# OV5640_Module_Connect.net
KiCad netlist of a schematic drawn in Altium Designer
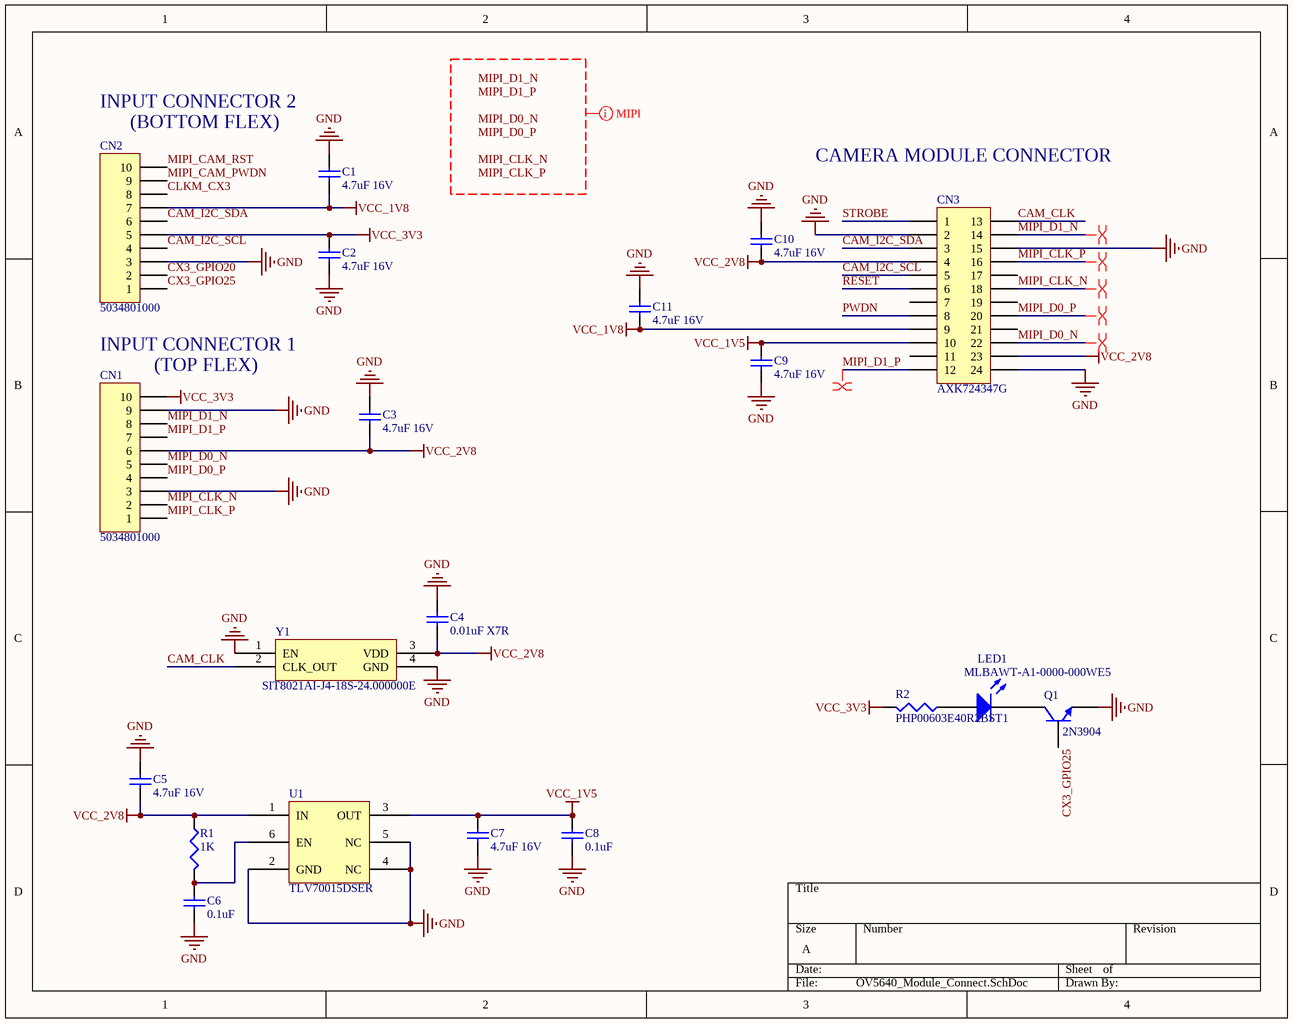
[diagram p0: OV5640_Module_Connect.SchDoc]

(export (version "E")
  (design (tool "Eeschema 10.0.6"))
  (components
    (comp (ref "C1")
      (value "4.7uF 16V")
      (footprint "1608[0603]")
      (description "Capacitor (Semiconductor SIM Model)")
      (fields (field (name "PUBLISHER") "Altium Limited"))
      (libsource (lib "Miscellaneous Devices") (part "Cap Semi"))
    )
    (comp (ref "C2")
      (value "4.7uF 16V")
      (footprint "1608[0603]")
      (description "Capacitor (Semiconductor SIM Model)")
      (fields (field (name "PUBLISHER") "Altium Limited"))
      (libsource (lib "Miscellaneous Devices") (part "Cap Semi"))
    )
    (comp (ref "C3")
      (value "4.7uF 16V")
      (footprint "1608[0603]")
      (description "Capacitor (Semiconductor SIM Model)")
      (fields (field (name "PUBLISHER") "Altium Limited"))
      (libsource (lib "Miscellaneous Devices") (part "Cap Semi"))
    )
    (comp (ref "C4")
      (value "0.01uF X7R")
      (footprint "0402")
      (description "Capacitor (Semiconductor SIM Model)")
      (fields (field (name "PUBLISHER") "Altium Limited"))
      (libsource (lib "Miscellaneous Devices") (part "Cap Semi"))
    )
    (comp (ref "C5")
      (value "4.7uF 16V")
      (footprint "1608[0603]")
      (description "Capacitor (Semiconductor SIM Model)")
      (fields (field (name "PUBLISHER") "Altium Limited"))
      (libsource (lib "Miscellaneous Devices") (part "Cap Semi"))
    )
    (comp (ref "C6")
      (value "0.1uF")
      (footprint "0402")
      (description "Capacitor (Semiconductor SIM Model)")
      (fields (field (name "PUBLISHER") "Altium Limited"))
      (libsource (lib "Miscellaneous Devices") (part "Cap Semi"))
    )
    (comp (ref "C7")
      (value "4.7uF 16V")
      (footprint "1608[0603]")
      (description "Capacitor (Semiconductor SIM Model)")
      (fields (field (name "PUBLISHER") "Altium Limited"))
      (libsource (lib "Miscellaneous Devices") (part "Cap Semi"))
    )
    (comp (ref "C8")
      (value "0.1uF")
      (footprint "0402")
      (description "Capacitor (Semiconductor SIM Model)")
      (fields (field (name "PUBLISHER") "Altium Limited"))
      (libsource (lib "Miscellaneous Devices") (part "Cap Semi"))
    )
    (comp (ref "C9")
      (value "4.7uF 16V")
      (footprint "1608[0603]")
      (description "Capacitor (Semiconductor SIM Model)")
      (fields (field (name "PUBLISHER") "Altium Limited"))
      (libsource (lib "Miscellaneous Devices") (part "Cap Semi"))
    )
    (comp (ref "C10")
      (value "4.7uF 16V")
      (footprint "1608[0603]")
      (description "Capacitor (Semiconductor SIM Model)")
      (fields (field (name "PUBLISHER") "Altium Limited"))
      (libsource (lib "Miscellaneous Devices") (part "Cap Semi"))
    )
    (comp (ref "C11")
      (value "4.7uF 16V")
      (footprint "1608[0603]")
      (description "Capacitor (Semiconductor SIM Model)")
      (fields (field (name "PUBLISHER") "Altium Limited"))
      (libsource (lib "Miscellaneous Devices") (part "Cap Semi"))
    )
    (comp (ref "CN1")
      (value "5034801000")
      (footprint "5034801000")
      (description "Header, 10-Pin")
      (fields (field (name "PUBLISHER") "Altium Limited"))
      (libsource (lib "Miscellaneous Connectors") (part "Header 10"))
    )
    (comp (ref "CN2")
      (value "5034801000")
      (footprint "5034801000")
      (description "Header, 10-Pin")
      (fields (field (name "PUBLISHER") "Altium Limited"))
      (libsource (lib "Miscellaneous Connectors") (part "Header 10"))
    )
    (comp (ref "CN3")
      (value "AXK724347G")
      (footprint "AXK724347G")
      (description "Header, 12-Pin, Dual row")
      (fields (field (name "PUBLISHER") "Altium Limited"))
      (libsource (lib "Miscellaneous Connectors") (part "Header 12X2A"))
    )
    (comp (ref "LED1")
      (value "MLBAWT-A1-0000-000WE5")
      (footprint "Cree ML-B LEB")
      (description "Typical BLUE SiC LED")
      (fields (field (name "PUBLISHER") "Altium Limited"))
      (libsource (lib "Miscellaneous Devices") (part "LED3"))
    )
    (comp (ref "Q1")
      (value "2N3904")
      (footprint "SOT-23")
      (description "NPN General Purpose Amplifier")
      (fields (field (name "PUBLISHER") "Altium Limited"))
      (libsource (lib "Miscellaneous Devices") (part "2N3904"))
    )
    (comp (ref "R1")
      (value "1K")
      (footprint "0402")
      (description "Resistor")
      (fields (field (name "PUBLISHER") "Altium Limited"))
      (libsource (lib "Miscellaneous Devices") (part "Res3"))
    )
    (comp (ref "R2")
      (value "PHP00603E40R2BST1")
      (footprint "J1-0603")
      (description "Resistor")
      (fields (field (name "PUBLISHER") "Altium Limited"))
      (libsource (lib "Miscellaneous Devices") (part "Res3"))
    )
    (comp (ref "U1")
      (value "TLV70015DSER")
      (footprint "TLV70015DSER")
      (libsource (lib "CX3_Camera") (part "TLV70015DSER"))
    )
    (comp (ref "Y1")
      (value "SIT8021AI-J4-18S-24.000000E")
      (footprint "SIT8021AI-J4-18S-24.000000E")
      (libsource (lib "CX3_Camera") (part "OSCILLATOR_2"))
    )
  )
  (nets
    (net (code "1") (name "/CAM_CLK") (class "Default")
      (node (ref "CN3") (pin "13") (pinfunction "13_13") (pintype "passive"))
      (node (ref "Y1") (pin "2") (pinfunction "CLK_OUT_2") (pintype "passive"))
    )
    (net (code "2") (name "/CAM_I2C_SCL") (class "Default")
      (node (ref "CN2") (pin "4") (pinfunction "4_4") (pintype "passive"))
      (node (ref "CN3") (pin "5") (pinfunction "5_5") (pintype "passive"))
    )
    (net (code "3") (name "/CAM_I2C_SDA") (class "Default")
      (node (ref "CN2") (pin "6") (pinfunction "6_6") (pintype "passive"))
      (node (ref "CN3") (pin "3") (pinfunction "3_3") (pintype "passive"))
    )
    (net (code "4") (name "/CLKM_CX3") (class "Default")
      (node (ref "CN2") (pin "8") (pinfunction "8_8") (pintype "passive"))
    )
    (net (code "5") (name "/CX3_GPIO20") (class "Default")
      (node (ref "CN2") (pin "2") (pinfunction "2_2") (pintype "passive"))
    )
    (net (code "6") (name "/CX3_GPIO25") (class "Default")
      (node (ref "CN2") (pin "1") (pinfunction "1_1") (pintype "passive"))
      (node (ref "Q1") (pin "2") (pinfunction "B_2") (pintype "passive"))
    )
    (net (code "7") (name "/MIPI_CAM_PWDN") (class "Default")
      (node (ref "CN2") (pin "9") (pinfunction "9_9") (pintype "passive"))
    )
    (net (code "8") (name "/MIPI_CAM_RST") (class "Default")
      (node (ref "CN2") (pin "10") (pinfunction "10_10") (pintype "passive"))
    )
    (net (code "9") (name "/MIPI_CLK_N") (class "Default")
      (node (ref "CN1") (pin "2") (pinfunction "2_2") (pintype "passive"))
      (node (ref "CN3") (pin "18") (pinfunction "18_18") (pintype "passive"))
    )
    (net (code "10") (name "/MIPI_CLK_P") (class "Default")
      (node (ref "CN1") (pin "1") (pinfunction "1_1") (pintype "passive"))
      (node (ref "CN3") (pin "16") (pinfunction "16_16") (pintype "passive"))
    )
    (net (code "11") (name "/MIPI_D0_N") (class "Default")
      (node (ref "CN1") (pin "5") (pinfunction "5_5") (pintype "passive"))
      (node (ref "CN3") (pin "22") (pinfunction "22_22") (pintype "passive"))
    )
    (net (code "12") (name "/MIPI_D0_P") (class "Default")
      (node (ref "CN1") (pin "4") (pinfunction "4_4") (pintype "passive"))
      (node (ref "CN3") (pin "20") (pinfunction "20_20") (pintype "passive"))
    )
    (net (code "13") (name "/MIPI_D1_N") (class "Default")
      (node (ref "CN1") (pin "8") (pinfunction "8_8") (pintype "passive"))
      (node (ref "CN3") (pin "14") (pinfunction "14_14") (pintype "passive"))
    )
    (net (code "14") (name "/MIPI_D1_P") (class "Default")
      (node (ref "CN1") (pin "7") (pinfunction "7_7") (pintype "passive"))
      (node (ref "CN3") (pin "12") (pinfunction "12_12") (pintype "passive"))
    )
    (net (code "15") (name "/PWDN") (class "Default")
      (node (ref "CN3") (pin "8") (pinfunction "8_8") (pintype "passive"))
    )
    (net (code "16") (name "/RESET") (class "Default")
      (node (ref "CN3") (pin "6") (pinfunction "6_6") (pintype "passive"))
    )
    (net (code "17") (name "/STROBE") (class "Default")
      (node (ref "CN3") (pin "1") (pinfunction "1_1") (pintype "passive"))
    )
    (net (code "18") (name "GND") (class "Default")
      (node (ref "C1") (pin "2") (pinfunction "2_2") (pintype "passive"))
      (node (ref "C10") (pin "2") (pinfunction "2_2") (pintype "passive"))
      (node (ref "C11") (pin "2") (pinfunction "2_2") (pintype "passive"))
      (node (ref "C2") (pin "1") (pinfunction "1_1") (pintype "passive"))
      (node (ref "C3") (pin "2") (pinfunction "2_2") (pintype "passive"))
      (node (ref "C4") (pin "2") (pinfunction "2_2") (pintype "passive"))
      (node (ref "C5") (pin "2") (pinfunction "2_2") (pintype "passive"))
      (node (ref "C6") (pin "1") (pinfunction "1_1") (pintype "passive"))
      (node (ref "C7") (pin "1") (pinfunction "1_1") (pintype "passive"))
      (node (ref "C8") (pin "1") (pinfunction "1_1") (pintype "passive"))
      (node (ref "C9") (pin "1") (pinfunction "1_1") (pintype "passive"))
      (node (ref "CN1") (pin "3") (pinfunction "3_3") (pintype "passive"))
      (node (ref "CN1") (pin "9") (pinfunction "9_9") (pintype "passive"))
      (node (ref "CN2") (pin "3") (pinfunction "3_3") (pintype "passive"))
      (node (ref "CN3") (pin "15") (pinfunction "15_15") (pintype "passive"))
      (node (ref "CN3") (pin "2") (pinfunction "2_2") (pintype "passive"))
      (node (ref "CN3") (pin "24") (pinfunction "24_24") (pintype "passive"))
      (node (ref "Q1") (pin "1") (pinfunction "E_1") (pintype "passive"))
      (node (ref "U1") (pin "2") (pinfunction "GND_2") (pintype "passive"))
      (node (ref "U1") (pin "4") (pinfunction "NC_4") (pintype "passive"))
      (node (ref "U1") (pin "5") (pinfunction "NC_5") (pintype "passive"))
      (node (ref "Y1") (pin "1") (pinfunction "EN_1") (pintype "passive"))
      (node (ref "Y1") (pin "4") (pinfunction "GND_4") (pintype "passive"))
    )
    (net (code "19") (name "Net-(LED1-A)") (class "Default")
      (node (ref "LED1") (pin "1") (pinfunction "A_1") (pintype "passive"))
      (node (ref "R2") (pin "1") (pinfunction "1_1") (pintype "passive"))
    )
    (net (code "20") (name "Net-(LED1-K)") (class "Default")
      (node (ref "LED1") (pin "2") (pinfunction "K_2") (pintype "passive"))
      (node (ref "Q1") (pin "3") (pinfunction "C_3") (pintype "passive"))
    )
    (net (code "21") (name "Net-(U1-EN)") (class "Default")
      (node (ref "C6") (pin "2") (pinfunction "2_2") (pintype "passive"))
      (node (ref "R1") (pin "2") (pinfunction "2_2") (pintype "passive"))
      (node (ref "U1") (pin "6") (pinfunction "EN_6") (pintype "passive"))
    )
    (net (code "22") (name "VCC_1V5") (class "Default")
      (node (ref "C7") (pin "2") (pinfunction "2_2") (pintype "passive"))
      (node (ref "C8") (pin "2") (pinfunction "2_2") (pintype "passive"))
      (node (ref "C9") (pin "2") (pinfunction "2_2") (pintype "passive"))
      (node (ref "CN3") (pin "10") (pinfunction "10_10") (pintype "passive"))
      (node (ref "U1") (pin "3") (pinfunction "OUT_3") (pintype "passive"))
    )
    (net (code "23") (name "VCC_1V8") (class "Default")
      (node (ref "C1") (pin "1") (pinfunction "1_1") (pintype "passive"))
      (node (ref "C11") (pin "1") (pinfunction "1_1") (pintype "passive"))
      (node (ref "CN2") (pin "7") (pinfunction "7_7") (pintype "passive"))
      (node (ref "CN3") (pin "9") (pinfunction "9_9") (pintype "passive"))
    )
    (net (code "24") (name "VCC_2V8") (class "Default")
      (node (ref "C10") (pin "1") (pinfunction "1_1") (pintype "passive"))
      (node (ref "C3") (pin "1") (pinfunction "1_1") (pintype "passive"))
      (node (ref "C4") (pin "1") (pinfunction "1_1") (pintype "passive"))
      (node (ref "C5") (pin "1") (pinfunction "1_1") (pintype "passive"))
      (node (ref "CN1") (pin "6") (pinfunction "6_6") (pintype "passive"))
      (node (ref "CN3") (pin "23") (pinfunction "23_23") (pintype "passive"))
      (node (ref "CN3") (pin "4") (pinfunction "4_4") (pintype "passive"))
      (node (ref "R1") (pin "1") (pinfunction "1_1") (pintype "passive"))
      (node (ref "U1") (pin "1") (pinfunction "IN_1") (pintype "passive"))
      (node (ref "Y1") (pin "3") (pinfunction "VDD_3") (pintype "passive"))
    )
    (net (code "25") (name "VCC_3V3") (class "Default")
      (node (ref "C2") (pin "2") (pinfunction "2_2") (pintype "passive"))
      (node (ref "CN1") (pin "10") (pinfunction "10_10") (pintype "passive"))
      (node (ref "CN2") (pin "5") (pinfunction "5_5") (pintype "passive"))
      (node (ref "R2") (pin "2") (pinfunction "2_2") (pintype "passive"))
    )
    (net (code "26") (name "unconnected-(CN3-Pad7)") (class "Default")
      (node (ref "CN3") (pin "7") (pinfunction "7_7") (pintype "passive"))
    )
    (net (code "27") (name "unconnected-(CN3-Pad11)") (class "Default")
      (node (ref "CN3") (pin "11") (pinfunction "11_11") (pintype "passive"))
    )
    (net (code "28") (name "unconnected-(CN3-Pad17)") (class "Default")
      (node (ref "CN3") (pin "17") (pinfunction "17_17") (pintype "passive"))
    )
    (net (code "29") (name "unconnected-(CN3-Pad19)") (class "Default")
      (node (ref "CN3") (pin "19") (pinfunction "19_19") (pintype "passive"))
    )
    (net (code "30") (name "unconnected-(CN3-Pad21)") (class "Default")
      (node (ref "CN3") (pin "21") (pinfunction "21_21") (pintype "passive"))
    )
  )
)
